# Sheet1.net
KiCad netlist of a schematic drawn in Altium Designer
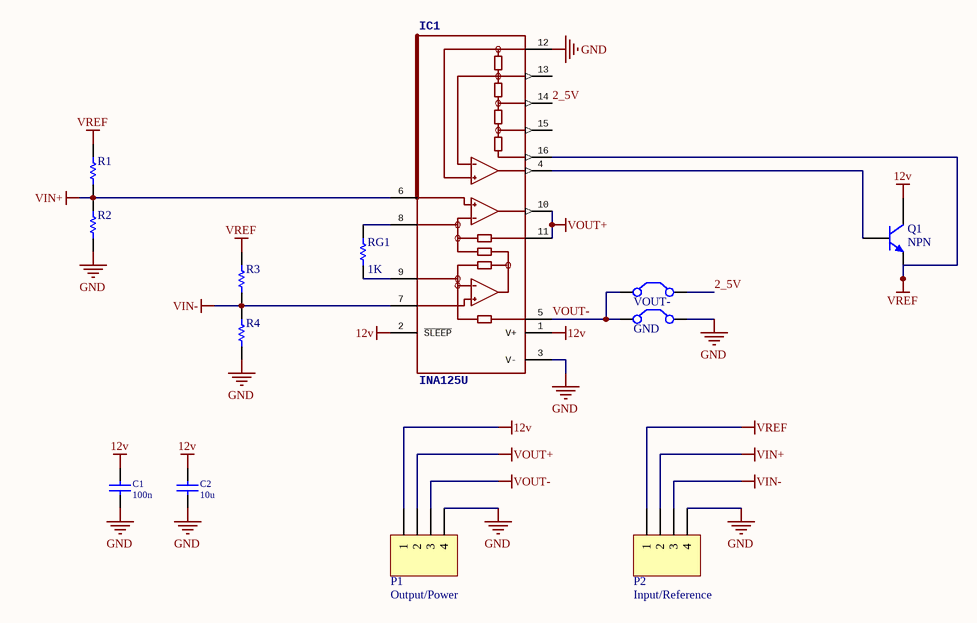
[diagram p0: Sheet1.SchDoc]

(export (version "E")
  (design (tool "Eeschema 10.0.6"))
  (components
    (comp (ref "C1")
      (value "100n")
      (footprint "C1206")
      (description "Capacitor")
      (libsource (lib "SpiritLevel_2E") (part "CAP_1"))
    )
    (comp (ref "C2")
      (value "10u")
      (footprint "SMD CAPACITOR 220UF 16V")
      (description "Capacitor")
      (libsource (lib "SpiritLevel_2E") (part "CAP_1"))
    )
    (comp (ref "IC1")
      (value "INA125U")
      (footprint "SOIC16_M")
      (description "<b>Instrumentation Amplifier</b><p>\nwith Precision Voltage Reference")
      (fields (field (name "MF") "TEXAS INSTRUMENT CONNECTORS"))
      (libsource (lib "burr-brown") (part "INA125U"))
    )
    (comp (ref "P1")
      (value "Output/Power")
      (footprint "SMD 4Wire")
      (description "Header, 4-Pin")
      (fields (field (name "PUBLISHER") "Altium Limited"))
      (libsource (lib "Miscellaneous Connectors") (part "Header 4"))
    )
    (comp (ref "P2")
      (value "Input/Reference")
      (footprint "SMD 4Wire")
      (description "Header, 4-Pin")
      (fields (field (name "PUBLISHER") "Altium Limited"))
      (libsource (lib "Miscellaneous Connectors") (part "Header 4"))
    )
    (comp (ref "Q1")
      (value "NPN")
      (footprint "TO220_SMD_BENT")
      (description "NPN Bipolar Transistor")
      (fields (field (name "PUBLISHER") "Altium Limited"))
      (libsource (lib "Miscellaneous Devices") (part "NPN"))
    )
    (comp (ref "R1")
      (value "Res1")
      (footprint "R0805")
      (description "Resistor")
      (fields (field (name "PUBLISHER") "Altium Limited"))
      (libsource (lib "Miscellaneous Devices") (part "Res1"))
    )
    (comp (ref "R2")
      (value "Res1")
      (footprint "R0805")
      (description "Resistor")
      (fields (field (name "PUBLISHER") "Altium Limited"))
      (libsource (lib "Miscellaneous Devices") (part "Res1"))
    )
    (comp (ref "R3")
      (value "Res1")
      (footprint "R0805")
      (description "Resistor")
      (fields (field (name "PUBLISHER") "Altium Limited"))
      (libsource (lib "Miscellaneous Devices") (part "Res1"))
    )
    (comp (ref "R4")
      (value "Res1")
      (footprint "R0805")
      (description "Resistor")
      (fields (field (name "PUBLISHER") "Altium Limited"))
      (libsource (lib "Miscellaneous Devices") (part "Res1"))
    )
    (comp (ref "RG1")
      (value "1K")
      (footprint "R0805")
      (description "Resistor")
      (fields (field (name "Comment") "Res1") (field (name "PUBLISHER") "Altium Limited"))
      (libsource (lib "Miscellaneous Devices") (part "Res1"))
    )
    (comp (ref "W5")
      (value "VOUT-")
      (footprint "Passives1:R0805")
      (description "Jumper Wire")
      (fields (field (name "PUBLISHER") "Altium Limited"))
      (libsource (lib "Miscellaneous Devices") (part "Jumper"))
    )
    (comp (ref "W6")
      (value "GND")
      (footprint "R0805")
      (description "Jumper Wire")
      (fields (field (name "PUBLISHER") "Altium Limited"))
      (libsource (lib "Miscellaneous Devices") (part "Jumper"))
    )
  )
  (nets
    (net (code "1") (name "/2_5V") (class "Default")
      (node (ref "IC1") (pin "14") (pinfunction "REF2.5_14") (pintype "output"))
      (node (ref "W5") (pin "2") (pinfunction "C2_2") (pintype "passive"))
    )
    (net (code "2") (name "12v") (class "Default")
      (node (ref "C1") (pin "1") (pinfunction "1_1") (pintype "passive"))
      (node (ref "C2") (pin "1") (pinfunction "1_1") (pintype "passive"))
      (node (ref "IC1") (pin "1") (pinfunction "V+_1") (pintype "power_in"))
      (node (ref "IC1") (pin "2") (pinfunction "~{SLEEP}_2") (pintype "passive"))
      (node (ref "P1") (pin "1") (pinfunction "1_1") (pintype "passive"))
      (node (ref "Q1") (pin "2") (pinfunction "C_2") (pintype "passive"))
    )
    (net (code "3") (name "GND") (class "Default")
      (node (ref "C1") (pin "2") (pinfunction "2_2") (pintype "passive"))
      (node (ref "C2") (pin "2") (pinfunction "2_2") (pintype "passive"))
      (node (ref "IC1") (pin "12") (pinfunction "REFCOM_12") (pintype "passive"))
      (node (ref "IC1") (pin "3") (pinfunction "V-_3") (pintype "power_in"))
      (node (ref "P1") (pin "4") (pinfunction "4_4") (pintype "passive"))
      (node (ref "P2") (pin "4") (pinfunction "4_4") (pintype "passive"))
      (node (ref "R2") (pin "1") (pinfunction "1_1") (pintype "passive"))
      (node (ref "R4") (pin "1") (pinfunction "1_1") (pintype "passive"))
      (node (ref "W6") (pin "2") (pinfunction "C2_2") (pintype "passive"))
    )
    (net (code "4") (name "Net-(IC1-REFOUT)") (class "Default")
      (node (ref "IC1") (pin "4") (pinfunction "REFOUT_4") (pintype "output"))
      (node (ref "Q1") (pin "3") (pinfunction "B_3") (pintype "passive"))
    )
    (net (code "5") (name "Net-(IC1-RG-Pad8)") (class "Default")
      (node (ref "IC1") (pin "8") (pinfunction "RG_8") (pintype "passive"))
      (node (ref "RG1") (pin "2") (pinfunction "2_2") (pintype "passive"))
    )
    (net (code "6") (name "Net-(IC1-RG-Pad9)") (class "Default")
      (node (ref "IC1") (pin "9") (pinfunction "RG_9") (pintype "passive"))
      (node (ref "RG1") (pin "1") (pinfunction "1_1") (pintype "passive"))
    )
    (net (code "7") (name "VIN+") (class "Default")
      (node (ref "IC1") (pin "6") (pinfunction "+IN_6") (pintype "passive"))
      (node (ref "P2") (pin "2") (pinfunction "2_2") (pintype "passive"))
      (node (ref "R1") (pin "1") (pinfunction "1_1") (pintype "passive"))
      (node (ref "R2") (pin "2") (pinfunction "2_2") (pintype "passive"))
    )
    (net (code "8") (name "VIN-") (class "Default")
      (node (ref "IC1") (pin "7") (pinfunction "-IN_7") (pintype "passive"))
      (node (ref "P2") (pin "3") (pinfunction "3_3") (pintype "passive"))
      (node (ref "R3") (pin "1") (pinfunction "1_1") (pintype "passive"))
      (node (ref "R4") (pin "2") (pinfunction "2_2") (pintype "passive"))
    )
    (net (code "9") (name "VOUT+") (class "Default")
      (node (ref "IC1") (pin "10") (pinfunction "OUT_10") (pintype "output"))
      (node (ref "IC1") (pin "11") (pinfunction "SENSE_11") (pintype "passive"))
      (node (ref "P1") (pin "2") (pinfunction "2_2") (pintype "passive"))
    )
    (net (code "10") (name "VOUT-") (class "Default")
      (node (ref "IC1") (pin "5") (pinfunction "REF_5") (pintype "passive"))
      (node (ref "P1") (pin "3") (pinfunction "3_3") (pintype "passive"))
      (node (ref "W5") (pin "1") (pinfunction "C1_1") (pintype "passive"))
      (node (ref "W6") (pin "1") (pinfunction "C1_1") (pintype "passive"))
    )
    (net (code "11") (name "VREF") (class "Default")
      (node (ref "IC1") (pin "16") (pinfunction "REF10_16") (pintype "output"))
      (node (ref "P2") (pin "1") (pinfunction "1_1") (pintype "passive"))
      (node (ref "Q1") (pin "1") (pinfunction "E_1") (pintype "passive"))
      (node (ref "R1") (pin "2") (pinfunction "2_2") (pintype "passive"))
      (node (ref "R3") (pin "2") (pinfunction "2_2") (pintype "passive"))
    )
    (net (code "12") (name "unconnected-(IC1-REF5-Pad15)") (class "Default")
      (node (ref "IC1") (pin "15") (pinfunction "REF5_15") (pintype "output"))
    )
    (net (code "13") (name "unconnected-(IC1-REFBG-Pad13)") (class "Default")
      (node (ref "IC1") (pin "13") (pinfunction "REFBG_13") (pintype "output"))
    )
  )
)
